# tester.net
KiCad netlist of a schematic drawn in Altium Designer
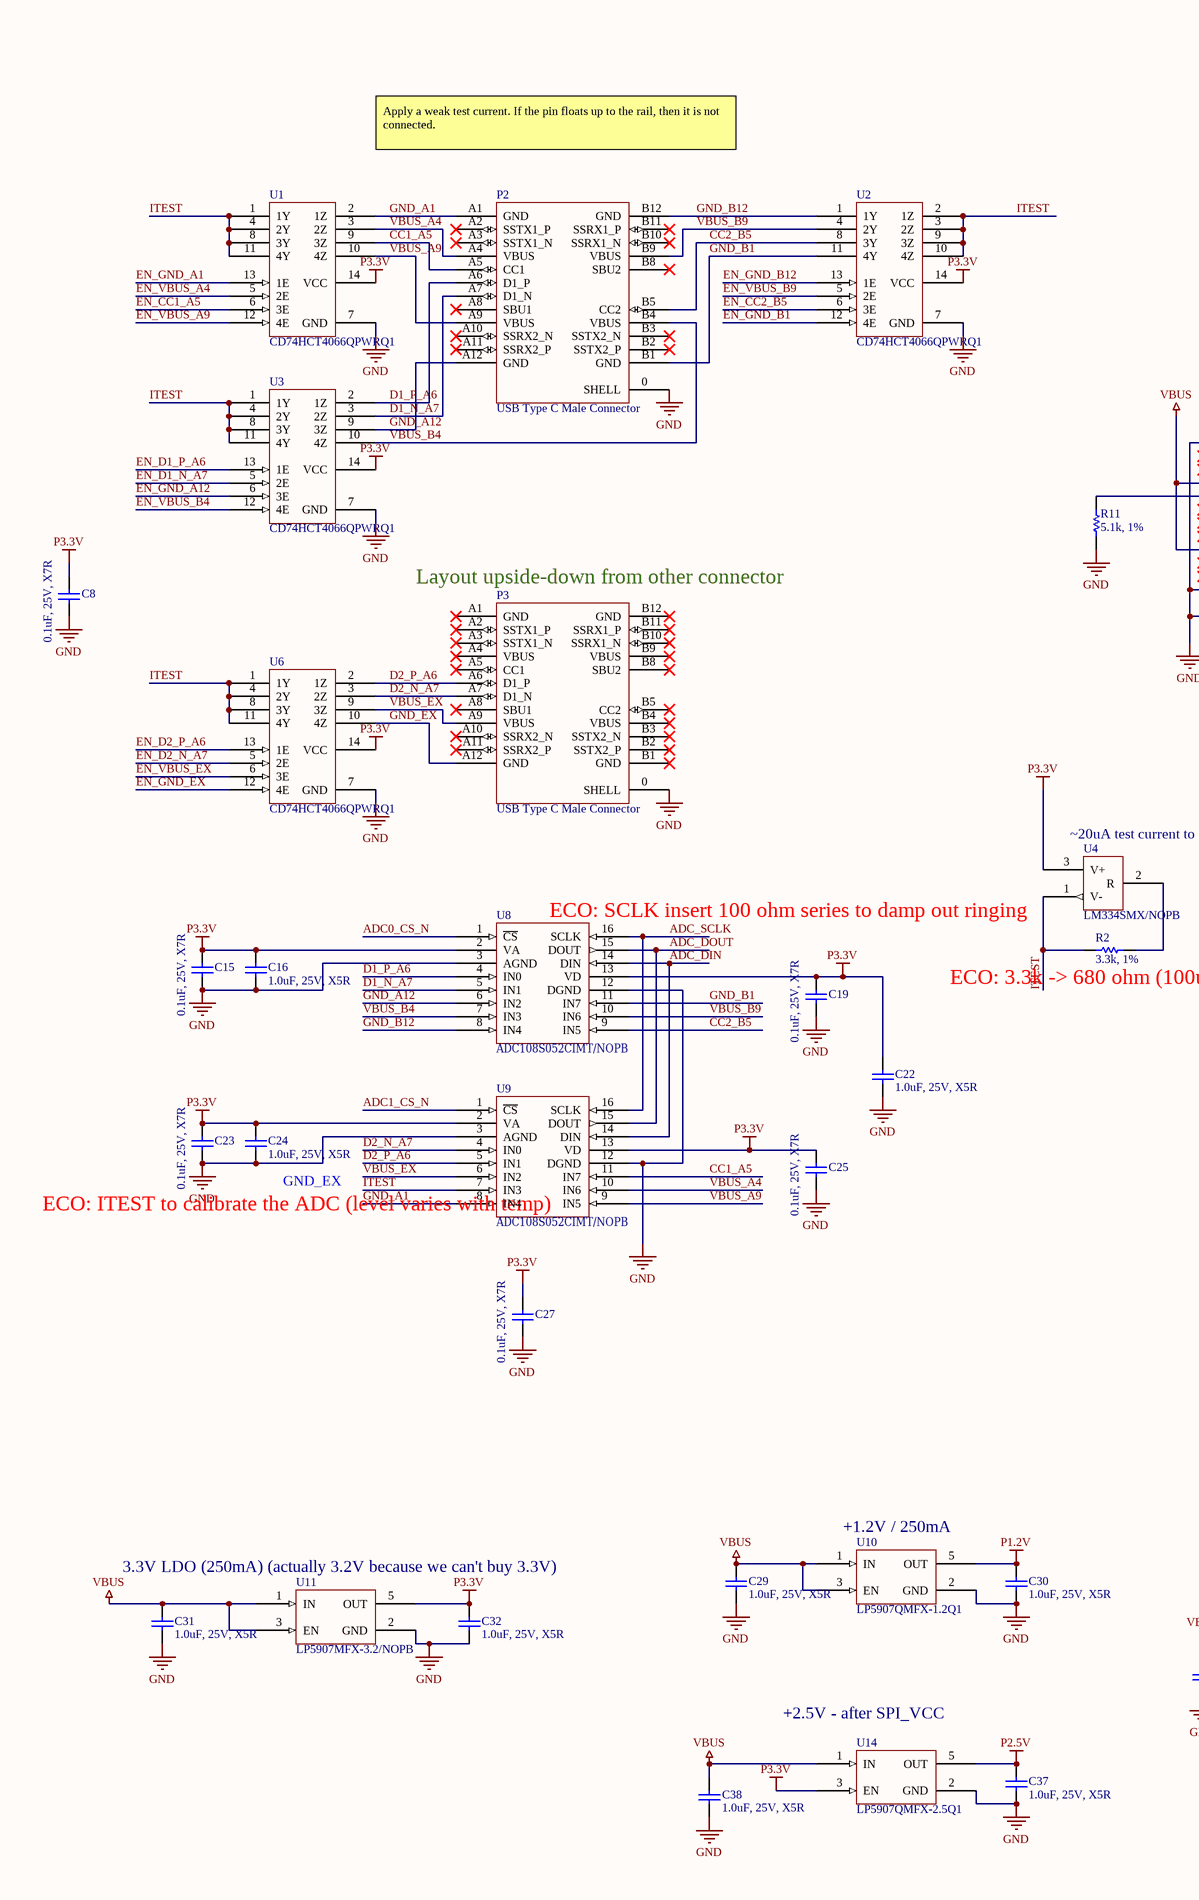
[diagram p0: tester.SchDoc, left]
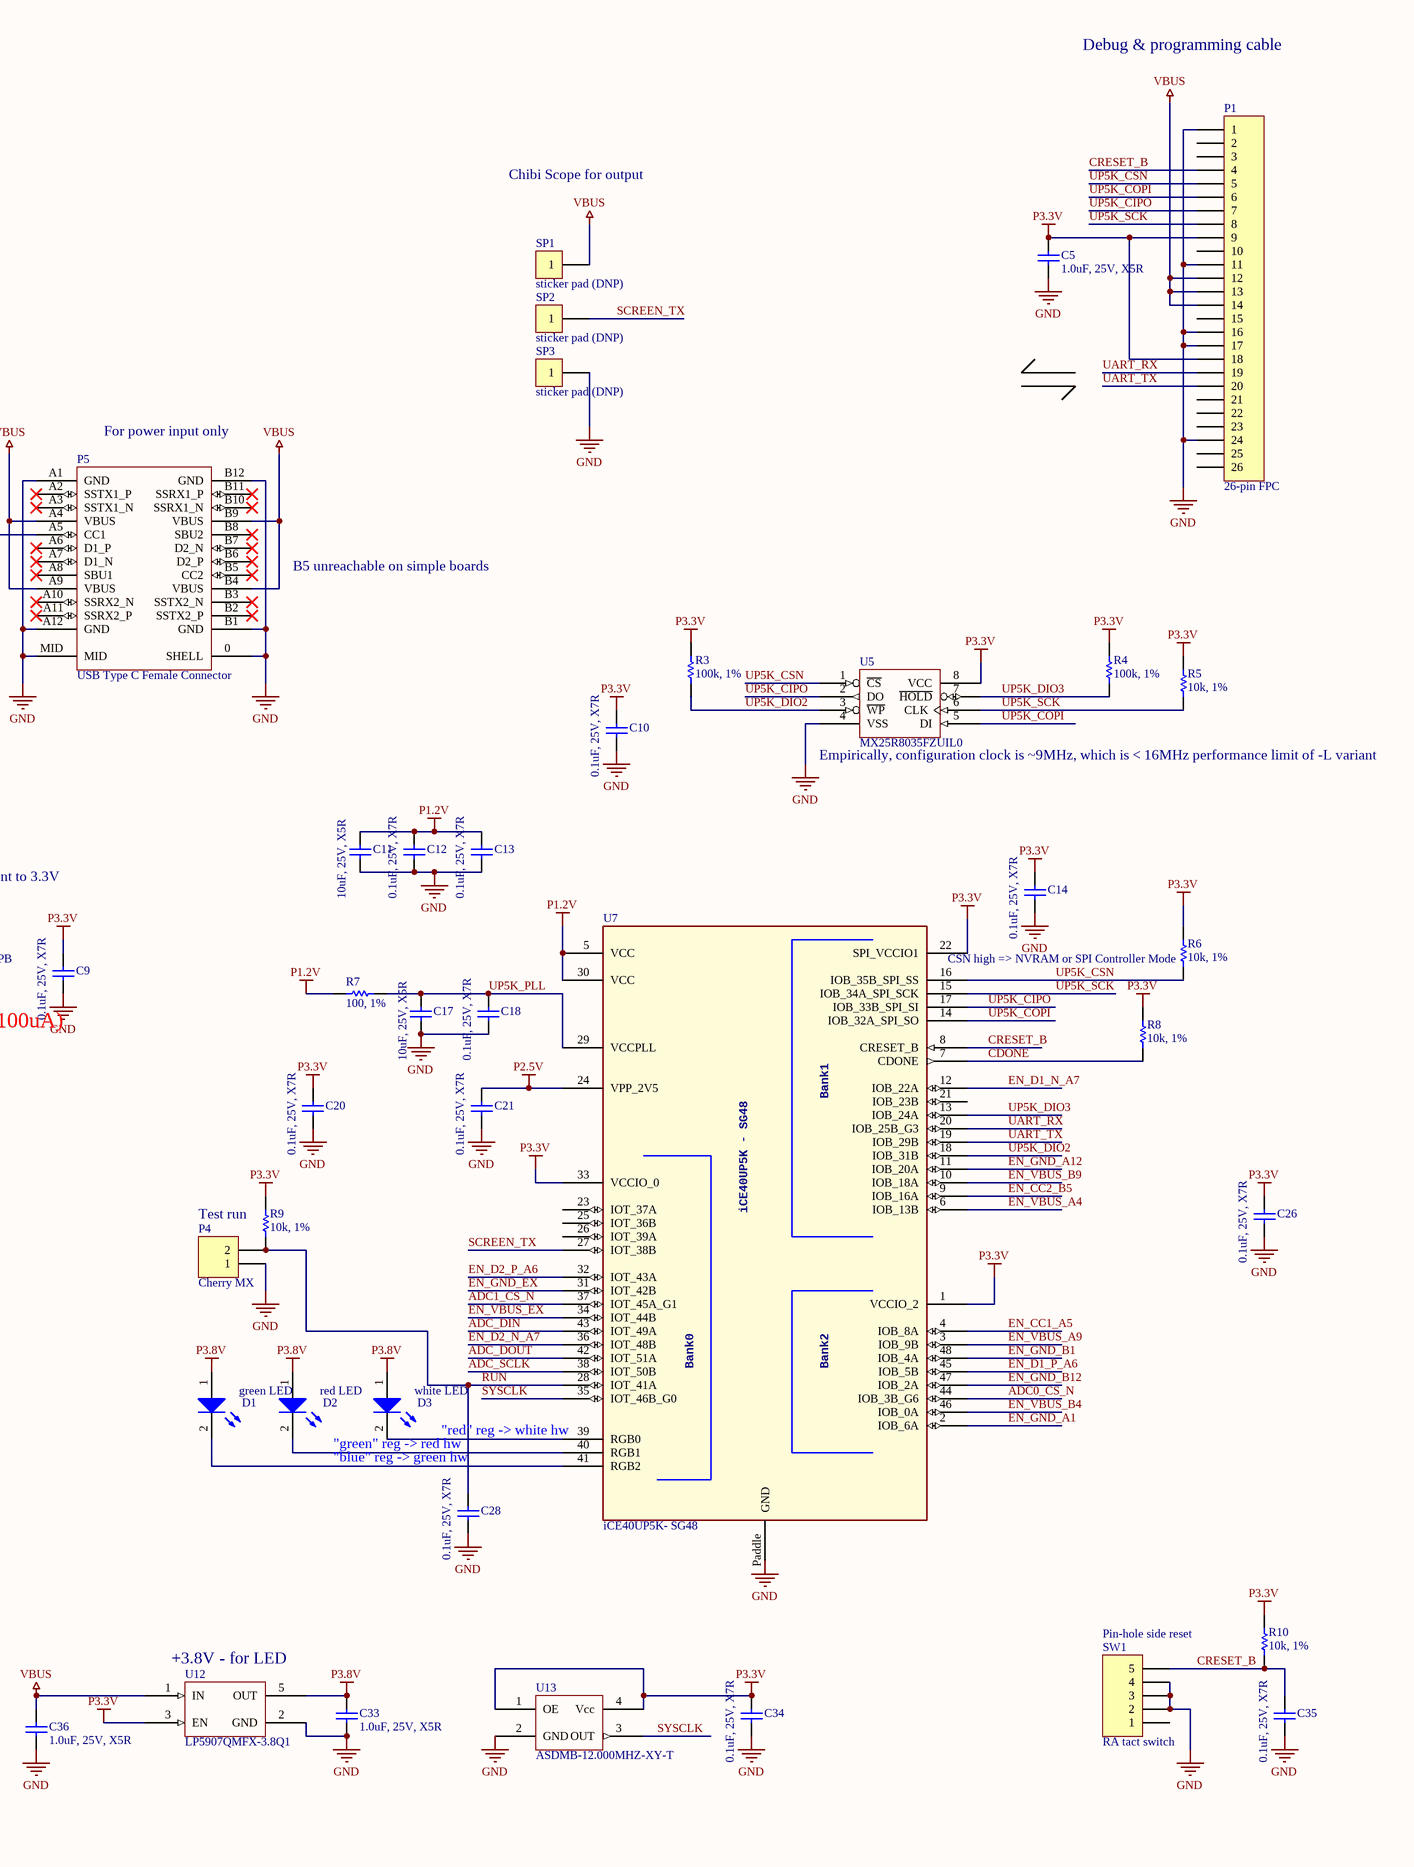
[diagram p1: tester.SchDoc, right]

(export (version "E")
  (design (tool "Eeschema 10.0.6"))
  (components
    (comp (ref "C5")
      (value "1.0uF, 25V, X5R")
      (footprint "B_CAP0603")
      (description "Capacitor (Semiconductor SIM Model)")
      (fields (field (name "MPN") "CL10A105KA8NNNC"))
      (libsource (lib "Miscellaneous Devices") (part "Cap Semi"))
    )
    (comp (ref "C8")
      (value "0.1uF, 25V, X7R")
      (footprint "B_CAP0603")
      (description "Capacitor (Semiconductor SIM Model)")
      (fields (field (name "MPN") "CC0603KRX7R8BB104"))
      (libsource (lib "Miscellaneous Devices") (part "Cap Semi"))
    )
    (comp (ref "C9")
      (value "0.1uF, 25V, X7R")
      (footprint "B_CAP0603")
      (description "Capacitor (Semiconductor SIM Model)")
      (fields (field (name "MPN") "CC0603KRX7R8BB104"))
      (libsource (lib "Miscellaneous Devices") (part "Cap Semi"))
    )
    (comp (ref "C10")
      (value "0.1uF, 25V, X7R")
      (footprint "B_CAP0603")
      (description "Capacitor (Semiconductor SIM Model)")
      (fields (field (name "MPN") "CC0603KRX7R8BB104"))
      (libsource (lib "Miscellaneous Devices") (part "Cap Semi"))
    )
    (comp (ref "C11")
      (value "10uF, 25V, X5R")
      (footprint "B_CAP0805")
      (description "Capacitor (Semiconductor SIM Model)")
      (fields (field (name "MPN") "GRM21BR61E106KA73L"))
      (libsource (lib "Miscellaneous Devices") (part "Cap Semi"))
    )
    (comp (ref "C12")
      (value "0.1uF, 25V, X7R")
      (footprint "B_CAP0603")
      (description "Capacitor (Semiconductor SIM Model)")
      (fields (field (name "MPN") "CC0603KRX7R8BB104"))
      (libsource (lib "Miscellaneous Devices") (part "Cap Semi"))
    )
    (comp (ref "C13")
      (value "0.1uF, 25V, X7R")
      (footprint "B_CAP0603")
      (description "Capacitor (Semiconductor SIM Model)")
      (fields (field (name "MPN") "CC0603KRX7R8BB104"))
      (libsource (lib "Miscellaneous Devices") (part "Cap Semi"))
    )
    (comp (ref "C14")
      (value "0.1uF, 25V, X7R")
      (footprint "B_CAP0603")
      (description "Capacitor (Semiconductor SIM Model)")
      (fields (field (name "MPN") "CC0603KRX7R8BB104"))
      (libsource (lib "Miscellaneous Devices") (part "Cap Semi"))
    )
    (comp (ref "C15")
      (value "0.1uF, 25V, X7R")
      (footprint "B_CAP0603")
      (description "Capacitor (Semiconductor SIM Model)")
      (fields (field (name "MPN") "CC0603KRX7R8BB104"))
      (libsource (lib "Miscellaneous Devices") (part "Cap Semi"))
    )
    (comp (ref "C16")
      (value "1.0uF, 25V, X5R")
      (footprint "B_CAP0603")
      (description "Capacitor (Semiconductor SIM Model)")
      (fields (field (name "MPN") "CL10A105KA8NNNC"))
      (libsource (lib "Miscellaneous Devices") (part "Cap Semi"))
    )
    (comp (ref "C17")
      (value "10uF, 25V, X5R")
      (footprint "B_CAP0805")
      (description "Capacitor (Semiconductor SIM Model)")
      (fields (field (name "MPN") "GRM21BR61E106KA73L"))
      (libsource (lib "Miscellaneous Devices") (part "Cap Semi"))
    )
    (comp (ref "C18")
      (value "0.1uF, 25V, X7R")
      (footprint "B_CAP0603")
      (description "Capacitor (Semiconductor SIM Model)")
      (fields (field (name "MPN") "CC0603KRX7R8BB104"))
      (libsource (lib "Miscellaneous Devices") (part "Cap Semi"))
    )
    (comp (ref "C19")
      (value "0.1uF, 25V, X7R")
      (footprint "B_CAP0603")
      (description "Capacitor (Semiconductor SIM Model)")
      (fields (field (name "MPN") "CC0603KRX7R8BB104"))
      (libsource (lib "Miscellaneous Devices") (part "Cap Semi"))
    )
    (comp (ref "C20")
      (value "0.1uF, 25V, X7R")
      (footprint "B_CAP0603")
      (description "Capacitor (Semiconductor SIM Model)")
      (fields (field (name "MPN") "CC0603KRX7R8BB104"))
      (libsource (lib "Miscellaneous Devices") (part "Cap Semi"))
    )
    (comp (ref "C21")
      (value "0.1uF, 25V, X7R")
      (footprint "B_CAP0603")
      (description "Capacitor (Semiconductor SIM Model)")
      (fields (field (name "MPN") "CC0603KRX7R8BB104"))
      (libsource (lib "Miscellaneous Devices") (part "Cap Semi"))
    )
    (comp (ref "C22")
      (value "1.0uF, 25V, X5R")
      (footprint "B_CAP0603")
      (description "Capacitor (Semiconductor SIM Model)")
      (fields (field (name "MPN") "CL10A105KA8NNNC"))
      (libsource (lib "Miscellaneous Devices") (part "Cap Semi"))
    )
    (comp (ref "C23")
      (value "0.1uF, 25V, X7R")
      (footprint "B_CAP0603")
      (description "Capacitor (Semiconductor SIM Model)")
      (fields (field (name "MPN") "CC0603KRX7R8BB104"))
      (libsource (lib "Miscellaneous Devices") (part "Cap Semi"))
    )
    (comp (ref "C24")
      (value "1.0uF, 25V, X5R")
      (footprint "B_CAP0603")
      (description "Capacitor (Semiconductor SIM Model)")
      (fields (field (name "MPN") "CL10A105KA8NNNC"))
      (libsource (lib "Miscellaneous Devices") (part "Cap Semi"))
    )
    (comp (ref "C25")
      (value "0.1uF, 25V, X7R")
      (footprint "B_CAP0603")
      (description "Capacitor (Semiconductor SIM Model)")
      (fields (field (name "MPN") "CC0603KRX7R8BB104"))
      (libsource (lib "Miscellaneous Devices") (part "Cap Semi"))
    )
    (comp (ref "C26")
      (value "0.1uF, 25V, X7R")
      (footprint "B_CAP0603")
      (description "Capacitor (Semiconductor SIM Model)")
      (fields (field (name "MPN") "CC0603KRX7R8BB104"))
      (libsource (lib "Miscellaneous Devices") (part "Cap Semi"))
    )
    (comp (ref "C27")
      (value "0.1uF, 25V, X7R")
      (footprint "B_CAP0603")
      (description "Capacitor (Semiconductor SIM Model)")
      (fields (field (name "MPN") "CC0603KRX7R8BB104"))
      (libsource (lib "Miscellaneous Devices") (part "Cap Semi"))
    )
    (comp (ref "C28")
      (value "0.1uF, 25V, X7R")
      (footprint "B_CAP0603")
      (description "Capacitor (Semiconductor SIM Model)")
      (fields (field (name "MPN") "CC0603KRX7R8BB104"))
      (libsource (lib "Miscellaneous Devices") (part "Cap Semi"))
    )
    (comp (ref "C29")
      (value "1.0uF, 25V, X5R")
      (footprint "B_CAP0603")
      (description "Capacitor (Semiconductor SIM Model)")
      (fields (field (name "MPN") "CL10A105KA8NNNC"))
      (libsource (lib "Miscellaneous Devices") (part "Cap Semi"))
    )
    (comp (ref "C30")
      (value "1.0uF, 25V, X5R")
      (footprint "B_CAP0603")
      (description "Capacitor (Semiconductor SIM Model)")
      (fields (field (name "MPN") "CL10A105KA8NNNC"))
      (libsource (lib "Miscellaneous Devices") (part "Cap Semi"))
    )
    (comp (ref "C31")
      (value "1.0uF, 25V, X5R")
      (footprint "B_CAP0603")
      (description "Capacitor (Semiconductor SIM Model)")
      (fields (field (name "MPN") "CL10A105KA8NNNC"))
      (libsource (lib "Miscellaneous Devices") (part "Cap Semi"))
    )
    (comp (ref "C32")
      (value "1.0uF, 25V, X5R")
      (footprint "B_CAP0603")
      (description "Capacitor (Semiconductor SIM Model)")
      (fields (field (name "MPN") "CL10A105KA8NNNC"))
      (libsource (lib "Miscellaneous Devices") (part "Cap Semi"))
    )
    (comp (ref "C33")
      (value "1.0uF, 25V, X5R")
      (footprint "B_CAP0603")
      (description "Capacitor (Semiconductor SIM Model)")
      (fields (field (name "MPN") "CL10A105KA8NNNC"))
      (libsource (lib "Miscellaneous Devices") (part "Cap Semi"))
    )
    (comp (ref "C34")
      (value "0.1uF, 25V, X7R")
      (footprint "B_CAP0603")
      (description "Capacitor (Semiconductor SIM Model)")
      (fields (field (name "MPN") "CC0603KRX7R8BB104"))
      (libsource (lib "Miscellaneous Devices") (part "Cap Semi"))
    )
    (comp (ref "C35")
      (value "0.1uF, 25V, X7R")
      (footprint "B_CAP0603")
      (description "Capacitor (Semiconductor SIM Model)")
      (fields (field (name "MPN") "CC0603KRX7R8BB104"))
      (libsource (lib "Miscellaneous Devices") (part "Cap Semi"))
    )
    (comp (ref "C36")
      (value "1.0uF, 25V, X5R")
      (footprint "B_CAP0603")
      (description "Capacitor (Semiconductor SIM Model)")
      (fields (field (name "MPN") "CL10A105KA8NNNC"))
      (libsource (lib "Miscellaneous Devices") (part "Cap Semi"))
    )
    (comp (ref "C37")
      (value "1.0uF, 25V, X5R")
      (footprint "B_CAP0603")
      (description "Capacitor (Semiconductor SIM Model)")
      (fields (field (name "MPN") "CL10A105KA8NNNC"))
      (libsource (lib "Miscellaneous Devices") (part "Cap Semi"))
    )
    (comp (ref "C38")
      (value "1.0uF, 25V, X5R")
      (footprint "B_CAP0603")
      (description "Capacitor (Semiconductor SIM Model)")
      (fields (field (name "MPN") "CL10A105KA8NNNC"))
      (libsource (lib "Miscellaneous Devices") (part "Cap Semi"))
    )
    (comp (ref "D1")
      (value "green LED")
      (footprint "B_LED0805")
      (description "Typical RED, GREEN, YELLOW, AMBER GaAs LED")
      (fields (field (name "MPN") "IN-S85ATG"))
      (libsource (lib "Miscellaneous Devices") (part "LED2"))
    )
    (comp (ref "D2")
      (value "red LED")
      (footprint "B_LED0805")
      (description "Typical RED, GREEN, YELLOW, AMBER GaAs LED")
      (fields (field (name "MPN") "IN-S85ATR"))
      (libsource (lib "Miscellaneous Devices") (part "LED2"))
    )
    (comp (ref "D3")
      (value "white LED")
      (footprint "B_LED0805")
      (description "Typical RED, GREEN, YELLOW, AMBER GaAs LED")
      (fields (field (name "MPN") "IN-S85AT5UW"))
      (libsource (lib "Miscellaneous Devices") (part "LED2"))
    )
    (comp (ref "P1")
      (value "26-pin FPC")
      (footprint "HRS_FH34SRJ-26S-0.5SH(50)")
      (description "26 Pin FPC header")
      (fields (field (name "MPN") "FH34SRJ-26S-0.5SH(99)"))
      (libsource (lib "commonsch-new") (part "FPC-26"))
    )
    (comp (ref "P2")
      (value "USB Type C Male Connector")
      (footprint "MOLEX_1054440001")
      (description "USB Type C Connector")
      (fields (field (name "MPN") "1054440011"))
      (libsource (lib "") (part "USB_TYPE_C_1"))
    )
    (comp (ref "P3")
      (value "USB Type C Male Connector")
      (footprint "MOLEX_1054440001")
      (description "USB Type C Connector")
      (fields (field (name "MPN") "1054440011"))
      (libsource (lib "") (part "USB_TYPE_C_1"))
    )
    (comp (ref "P4")
      (value "Cherry MX")
      (footprint "CHERRY_MX_BASIC")
      (description "Header, 2-Pin")
      (fields (field (name "MPN") "MX1A-E1NN") (field (name "PUBLISHER") "Altium Limited"))
      (libsource (lib "Miscellaneous Connectors") (part "Header 2"))
    )
    (comp (ref "P5")
      (value "USB Type C Female Connector")
      (footprint "TE_1-2295018-2")
      (description "USB Type C Connector")
      (fields (field (name "MPN") "1-2295018-2"))
      (libsource (lib "commonsch-new") (part "USB_TYPE_C"))
    )
    (comp (ref "R2")
      (value "3.3k, 1%")
      (footprint "B_RES0402")
      (description "Resistor")
      (fields (field (name "MPN") "TBD"))
      (libsource (lib "Miscellaneous Devices") (part "Res1"))
    )
    (comp (ref "R3")
      (value "100k, 1%")
      (footprint "B_RES0603")
      (description "Resistor")
      (fields (field (name "MPN") "TBD"))
      (libsource (lib "Miscellaneous Devices") (part "Res1"))
    )
    (comp (ref "R4")
      (value "100k, 1%")
      (footprint "B_RES0603")
      (description "Resistor")
      (fields (field (name "MPN") "TBD"))
      (libsource (lib "Miscellaneous Devices") (part "Res1"))
    )
    (comp (ref "R5")
      (value "10k, 1%")
      (footprint "B_RES0603")
      (description "Resistor")
      (fields (field (name "MPN") "RC0603FR-0710KL"))
      (libsource (lib "Miscellaneous Devices") (part "Res1"))
    )
    (comp (ref "R6")
      (value "10k, 1%")
      (footprint "B_RES0603")
      (description "Resistor")
      (fields (field (name "MPN") "RC0603FR-0710KL"))
      (libsource (lib "Miscellaneous Devices") (part "Res1"))
    )
    (comp (ref "R7")
      (value "100, 1%")
      (footprint "B_RES0603")
      (description "Resistor")
      (fields (field (name "MPN") "TBD"))
      (libsource (lib "Miscellaneous Devices") (part "Res1"))
    )
    (comp (ref "R8")
      (value "10k, 1%")
      (footprint "B_RES0603")
      (description "Resistor")
      (fields (field (name "MPN") "RC0603FR-0710KL"))
      (libsource (lib "Miscellaneous Devices") (part "Res1"))
    )
    (comp (ref "R9")
      (value "10k, 1%")
      (footprint "B_RES0603")
      (description "Resistor")
      (fields (field (name "MPN") "RC0603FR-0710KL"))
      (libsource (lib "Miscellaneous Devices") (part "Res1"))
    )
    (comp (ref "R10")
      (value "10k, 1%")
      (footprint "B_RES0603")
      (description "Resistor")
      (fields (field (name "MPN") "RC0603FR-0710KL"))
      (libsource (lib "Miscellaneous Devices") (part "Res1"))
    )
    (comp (ref "R11")
      (value "5.1k, 1%")
      (footprint "B_RES0603")
      (description "Resistor")
      (fields (field (name "MPN") "RC0603FR-075K1L"))
      (libsource (lib "Miscellaneous Devices") (part "Res1"))
    )
    (comp (ref "SP1")
      (value "sticker pad (DNP)")
      (footprint "TP_SMT_38mil")
      (description "Connector")
      (libsource (lib "*") (part "CON1"))
    )
    (comp (ref "SP2")
      (value "sticker pad (DNP)")
      (footprint "TP_SMT_38mil")
      (description "Connector")
      (libsource (lib "*") (part "CON1"))
    )
    (comp (ref "SP3")
      (value "sticker pad (DNP)")
      (footprint "TP_SMT_38mil")
      (description "Connector")
      (libsource (lib "*") (part "CON1"))
    )
    (comp (ref "SW1")
      (value "RA tact switch")
      (footprint "CK_KMS221GPLFS")
      (fields (field (name "MPN") "KMS221GPLFS") (field (name "PUBLISHER") "Altium Limited"))
      (libsource (lib "Miscellaneous Connectors") (part "Header 5"))
    )
    (comp (ref "U1")
      (value "CD74HCT4066QPWRQ1")
      (footprint "TSOP65P640-14AN")
      (description "4-channel analog mux")
      (libsource (lib "commonsch") (part "74HC4066"))
    )
    (comp (ref "U2")
      (value "CD74HCT4066QPWRQ1")
      (footprint "TSOP65P640-14AN")
      (description "4-channel analog mux")
      (libsource (lib "commonsch") (part "74HC4066"))
    )
    (comp (ref "U3")
      (value "CD74HCT4066QPWRQ1")
      (footprint "TSOP65P640-14AN")
      (description "4-channel analog mux")
      (libsource (lib "commonsch") (part "74HC4066"))
    )
    (comp (ref "U4")
      (value "LM334SMX/NOPB")
      (footprint "SOIC127P600-8AN")
      (description "LM134/234/334 3-terminal adjustable current sources")
      (libsource (lib "commonsch-new") (part "LMx34"))
    )
    (comp (ref "U5")
      (value "MX25R8035FZUIL0")
      (footprint "USON-8")
      (description "64Mbit SPI NOR FLASH")
      (libsource (lib "commonsch") (part "EN25P05-50GCP"))
    )
    (comp (ref "U6")
      (value "CD74HCT4066QPWRQ1")
      (footprint "TSOP65P640-14AN")
      (description "4-channel analog mux")
      (libsource (lib "commonsch") (part "74HC4066"))
    )
    (comp (ref "U7")
      (value "iCE40UP5K- SG48")
      (footprint "UP5K_QFN127P600-8N")
      (fields (field (name "MPN") "ICE40UP5K-SG48I"))
      (libsource (lib "LATTICEPLDS_Library") (part "iCE40UP5K- SG48"))
    )
    (comp (ref "U8")
      (value "ADC108S052CIMT/NOPB‎")
      (footprint "SOP65P640-16N")
      (description "12-input SPI ADC, bits & sample rate pin compatible across family")
      (fields (field (name "MPN") "ADC088S022CIMT/NOPB-ND"))
      (libsource (lib "commonsch") (part "ADCxx8Sxx2"))
    )
    (comp (ref "U9")
      (value "ADC108S052CIMT/NOPB‎")
      (footprint "SOP65P640-16N")
      (description "12-input SPI ADC, bits & sample rate pin compatible across family")
      (fields (field (name "MPN") "ADC088S022CIMT/NOPB-ND"))
      (libsource (lib "commonsch") (part "ADCxx8Sxx2"))
    )
    (comp (ref "U10")
      (value "LP5907QMFX-1.2Q1")
      (footprint "SOT23-5AN")
      (description "Ultra low-noise 250mA LDO for RF and analog in SOT23-5")
      (fields (field (name "MPN") "LP5907UVX-#.#/NOPB"))
      (libsource (lib "commonsch-new") (part "LP5907QMFX-XX"))
    )
    (comp (ref "U11")
      (value "LP5907MFX-3.2/NOPB")
      (footprint "SOT23-5AN")
      (description "Ultra low-noise 250mA LDO for RF and analog in SOT23-5")
      (fields (field (name "MPN") "LP5907UVX-#.#/NOPB"))
      (libsource (lib "commonsch-new") (part "LP5907QMFX-XX"))
    )
    (comp (ref "U12")
      (value "LP5907QMFX-3.8Q1")
      (footprint "SOT23-5AN")
      (description "Ultra low-noise 250mA LDO for RF and analog in SOT23-5")
      (fields (field (name "MPN") "LP5907UVX-#.#/NOPB"))
      (libsource (lib "commonsch-new") (part "LP5907QMFX-XX"))
    )
    (comp (ref "U13")
      (value "ASDMB-12.000MHZ-XY-T")
      (footprint "ABRACON_ASDMB")
      (description "Abracon ASDMB Miniature Oscillator")
      (libsource (lib "commonsch") (part "OSCILLATOR"))
    )
    (comp (ref "U14")
      (value "LP5907QMFX-2.5Q1")
      (footprint "SOT23-5AN")
      (description "Ultra low-noise 250mA LDO for RF and analog in SOT23-5")
      (fields (field (name "MPN") "LP5907UVX-#.#/NOPB"))
      (libsource (lib "commonsch-new") (part "LP5907QMFX-XX"))
    )
  )
  (nets
    (net (code "1") (name "/ADC0_CS_N") (class "Default")
      (node (ref "U7") (pin "44") (pinfunction "IOB_3B_G6_44") (pintype "bidirectional"))
      (node (ref "U8") (pin "1") (pinfunction "~{CS}_1") (pintype "input"))
    )
    (net (code "2") (name "/ADC1_CS_N") (class "Default")
      (node (ref "U7") (pin "37") (pinfunction "IOT_45A_G1_37") (pintype "bidirectional"))
      (node (ref "U9") (pin "1") (pinfunction "~{CS}_1") (pintype "input"))
    )
    (net (code "3") (name "/ADC_DIN") (class "Default")
      (node (ref "U7") (pin "43") (pinfunction "IOT_49A_43") (pintype "bidirectional"))
      (node (ref "U8") (pin "14") (pinfunction "DIN_14") (pintype "input"))
      (node (ref "U9") (pin "14") (pinfunction "DIN_14") (pintype "input"))
    )
    (net (code "4") (name "/ADC_DOUT") (class "Default")
      (node (ref "U7") (pin "42") (pinfunction "IOT_51A_42") (pintype "bidirectional"))
      (node (ref "U8") (pin "15") (pinfunction "DOUT_15") (pintype "output"))
      (node (ref "U9") (pin "15") (pinfunction "DOUT_15") (pintype "output"))
    )
    (net (code "5") (name "/ADC_SCLK") (class "Default")
      (node (ref "U7") (pin "38") (pinfunction "IOT_50B_38") (pintype "bidirectional"))
      (node (ref "U8") (pin "16") (pinfunction "SCLK_16") (pintype "input"))
      (node (ref "U9") (pin "16") (pinfunction "SCLK_16") (pintype "input"))
    )
    (net (code "6") (name "/CC1_A5") (class "Default")
      (node (ref "P2") (pin "A5") (pinfunction "CC1_A5") (pintype "bidirectional"))
      (node (ref "U1") (pin "9") (pinfunction "3Z_9") (pintype "passive"))
      (node (ref "U9") (pin "11") (pinfunction "IN7_11") (pintype "input"))
    )
    (net (code "7") (name "/CC2_B5") (class "Default")
      (node (ref "P2") (pin "B5") (pinfunction "CC2_B5") (pintype "bidirectional"))
      (node (ref "U2") (pin "8") (pinfunction "3Y_8") (pintype "passive"))
      (node (ref "U8") (pin "9") (pinfunction "IN5_9") (pintype "input"))
    )
    (net (code "8") (name "/CDONE") (class "Default")
      (node (ref "R8") (pin "2") (pinfunction "2_2") (pintype "passive"))
      (node (ref "U7") (pin "7") (pinfunction "CDONE_7") (pintype "output"))
    )
    (net (code "9") (name "/CRESET_B") (class "Default")
      (node (ref "C35") (pin "1") (pinfunction "1_1") (pintype "passive"))
      (node (ref "P1") (pin "4") (pinfunction "4_4") (pintype "passive"))
      (node (ref "R10") (pin "2") (pinfunction "2_2") (pintype "passive"))
      (node (ref "SW1") (pin "5") (pinfunction "5_5") (pintype "passive"))
      (node (ref "U7") (pin "8") (pinfunction "CRESET_B_8") (pintype "input"))
    )
    (net (code "10") (name "/D1_N_A7") (class "Default")
      (node (ref "P2") (pin "A7") (pinfunction "D1_N_A7") (pintype "bidirectional"))
      (node (ref "U3") (pin "3") (pinfunction "2Z_3") (pintype "passive"))
      (node (ref "U8") (pin "5") (pinfunction "IN1_5") (pintype "input"))
    )
    (net (code "11") (name "/D1_P_A6") (class "Default")
      (node (ref "P2") (pin "A6") (pinfunction "D1_P_A6") (pintype "bidirectional"))
      (node (ref "U3") (pin "2") (pinfunction "1Z_2") (pintype "passive"))
      (node (ref "U8") (pin "4") (pinfunction "IN0_4") (pintype "input"))
    )
    (net (code "12") (name "/D2_N_A7") (class "Default")
      (node (ref "P3") (pin "A7") (pinfunction "D1_N_A7") (pintype "bidirectional"))
      (node (ref "U6") (pin "3") (pinfunction "2Z_3") (pintype "passive"))
      (node (ref "U9") (pin "4") (pinfunction "IN0_4") (pintype "input"))
    )
    (net (code "13") (name "/D2_P_A6") (class "Default")
      (node (ref "P3") (pin "A6") (pinfunction "D1_P_A6") (pintype "bidirectional"))
      (node (ref "U6") (pin "2") (pinfunction "1Z_2") (pintype "passive"))
      (node (ref "U9") (pin "5") (pinfunction "IN1_5") (pintype "input"))
    )
    (net (code "14") (name "/EN_CC1_A5") (class "Default")
      (node (ref "U1") (pin "6") (pinfunction "3E_6") (pintype "input"))
      (node (ref "U7") (pin "4") (pinfunction "IOB_8A_4") (pintype "bidirectional"))
    )
    (net (code "15") (name "/EN_CC2_B5") (class "Default")
      (node (ref "U2") (pin "6") (pinfunction "3E_6") (pintype "input"))
      (node (ref "U7") (pin "9") (pinfunction "IOB_16A_9") (pintype "bidirectional"))
    )
    (net (code "16") (name "/EN_D1_N_A7") (class "Default")
      (node (ref "U3") (pin "5") (pinfunction "2E_5") (pintype "input"))
      (node (ref "U7") (pin "12") (pinfunction "IOB_22A_12") (pintype "bidirectional"))
    )
    (net (code "17") (name "/EN_D1_P_A6") (class "Default")
      (node (ref "U3") (pin "13") (pinfunction "1E_13") (pintype "input"))
      (node (ref "U7") (pin "45") (pinfunction "IOB_5B_45") (pintype "bidirectional"))
    )
    (net (code "18") (name "/EN_D2_N_A7") (class "Default")
      (node (ref "U6") (pin "5") (pinfunction "2E_5") (pintype "input"))
      (node (ref "U7") (pin "36") (pinfunction "IOT_48B_36") (pintype "bidirectional"))
    )
    (net (code "19") (name "/EN_D2_P_A6") (class "Default")
      (node (ref "U6") (pin "13") (pinfunction "1E_13") (pintype "input"))
      (node (ref "U7") (pin "32") (pinfunction "IOT_43A_32") (pintype "bidirectional"))
    )
    (net (code "20") (name "/EN_GND_A1") (class "Default")
      (node (ref "U1") (pin "13") (pinfunction "1E_13") (pintype "input"))
      (node (ref "U7") (pin "2") (pinfunction "IOB_6A_2") (pintype "bidirectional"))
    )
    (net (code "21") (name "/EN_GND_A12") (class "Default")
      (node (ref "U3") (pin "6") (pinfunction "3E_6") (pintype "input"))
      (node (ref "U7") (pin "11") (pinfunction "IOB_20A_11") (pintype "bidirectional"))
    )
    (net (code "22") (name "/EN_GND_B1") (class "Default")
      (node (ref "U2") (pin "12") (pinfunction "4E_12") (pintype "input"))
      (node (ref "U7") (pin "48") (pinfunction "IOB_4A_48") (pintype "bidirectional"))
    )
    (net (code "23") (name "/EN_GND_B12") (class "Default")
      (node (ref "U2") (pin "13") (pinfunction "1E_13") (pintype "input"))
      (node (ref "U7") (pin "47") (pinfunction "IOB_2A_47") (pintype "bidirectional"))
    )
    (net (code "24") (name "/EN_GND_EX") (class "Default")
      (node (ref "U6") (pin "12") (pinfunction "4E_12") (pintype "input"))
      (node (ref "U7") (pin "31") (pinfunction "IOT_42B_31") (pintype "bidirectional"))
    )
    (net (code "25") (name "/EN_VBUS_A4") (class "Default")
      (node (ref "U1") (pin "5") (pinfunction "2E_5") (pintype "input"))
      (node (ref "U7") (pin "6") (pinfunction "IOB_13B_6") (pintype "bidirectional"))
    )
    (net (code "26") (name "/EN_VBUS_A9") (class "Default")
      (node (ref "U1") (pin "12") (pinfunction "4E_12") (pintype "input"))
      (node (ref "U7") (pin "3") (pinfunction "IOB_9B_3") (pintype "bidirectional"))
    )
    (net (code "27") (name "/EN_VBUS_B4") (class "Default")
      (node (ref "U3") (pin "12") (pinfunction "4E_12") (pintype "input"))
      (node (ref "U7") (pin "46") (pinfunction "IOB_0A_46") (pintype "bidirectional"))
    )
    (net (code "28") (name "/EN_VBUS_B9") (class "Default")
      (node (ref "U2") (pin "5") (pinfunction "2E_5") (pintype "input"))
      (node (ref "U7") (pin "10") (pinfunction "IOB_18A_10") (pintype "bidirectional"))
    )
    (net (code "29") (name "/EN_VBUS_EX") (class "Default")
      (node (ref "U6") (pin "6") (pinfunction "3E_6") (pintype "input"))
      (node (ref "U7") (pin "34") (pinfunction "IOT_44B_34") (pintype "bidirectional"))
    )
    (net (code "30") (name "/GND_A1") (class "Default")
      (node (ref "P2") (pin "A1") (pinfunction "GND_A1") (pintype "power_in"))
      (node (ref "U1") (pin "2") (pinfunction "1Z_2") (pintype "passive"))
      (node (ref "U9") (pin "8") (pinfunction "IN4_8") (pintype "input"))
    )
    (net (code "31") (name "/GND_A12") (class "Default")
      (node (ref "P2") (pin "A12") (pinfunction "GND_A12") (pintype "power_in"))
      (node (ref "U3") (pin "9") (pinfunction "3Z_9") (pintype "passive"))
      (node (ref "U8") (pin "6") (pinfunction "IN2_6") (pintype "input"))
    )
    (net (code "32") (name "/GND_B1") (class "Default")
      (node (ref "P2") (pin "B1") (pinfunction "GND_B1") (pintype "power_in"))
      (node (ref "U2") (pin "11") (pinfunction "4Y_11") (pintype "passive"))
      (node (ref "U8") (pin "11") (pinfunction "IN7_11") (pintype "input"))
    )
    (net (code "33") (name "/GND_B12") (class "Default")
      (node (ref "P2") (pin "B12") (pinfunction "GND_B12") (pintype "power_in"))
      (node (ref "U2") (pin "1") (pinfunction "1Y_1") (pintype "passive"))
      (node (ref "U8") (pin "8") (pinfunction "IN4_8") (pintype "input"))
    )
    (net (code "34") (name "/GND_EX") (class "Default")
      (node (ref "P3") (pin "A12") (pinfunction "GND_A12") (pintype "power_in"))
      (node (ref "U6") (pin "10") (pinfunction "4Z_10") (pintype "passive"))
    )
    (net (code "35") (name "/ITEST") (class "Default")
      (node (ref "R2") (pin "1") (pinfunction "1_1") (pintype "passive"))
      (node (ref "U1") (pin "1") (pinfunction "1Y_1") (pintype "passive"))
      (node (ref "U1") (pin "11") (pinfunction "4Y_11") (pintype "passive"))
      (node (ref "U1") (pin "4") (pinfunction "2Y_4") (pintype "passive"))
      (node (ref "U1") (pin "8") (pinfunction "3Y_8") (pintype "passive"))
      (node (ref "U2") (pin "10") (pinfunction "4Z_10") (pintype "passive"))
      (node (ref "U2") (pin "2") (pinfunction "1Z_2") (pintype "passive"))
      (node (ref "U2") (pin "3") (pinfunction "2Z_3") (pintype "passive"))
      (node (ref "U2") (pin "9") (pinfunction "3Z_9") (pintype "passive"))
      (node (ref "U3") (pin "1") (pinfunction "1Y_1") (pintype "passive"))
      (node (ref "U3") (pin "11") (pinfunction "4Y_11") (pintype "passive"))
      (node (ref "U3") (pin "4") (pinfunction "2Y_4") (pintype "passive"))
      (node (ref "U3") (pin "8") (pinfunction "3Y_8") (pintype "passive"))
      (node (ref "U4") (pin "1") (pinfunction "V-_1") (pintype "output"))
      (node (ref "U6") (pin "1") (pinfunction "1Y_1") (pintype "passive"))
      (node (ref "U6") (pin "11") (pinfunction "4Y_11") (pintype "passive"))
      (node (ref "U6") (pin "4") (pinfunction "2Y_4") (pintype "passive"))
      (node (ref "U6") (pin "8") (pinfunction "3Y_8") (pintype "passive"))
      (node (ref "U9") (pin "7") (pinfunction "IN3_7") (pintype "input"))
    )
    (net (code "36") (name "/RUN") (class "Default")
      (node (ref "C28") (pin "1") (pinfunction "1_1") (pintype "passive"))
      (node (ref "P4") (pin "2") (pinfunction "2_2") (pintype "passive"))
      (node (ref "R9") (pin "2") (pinfunction "2_2") (pintype "passive"))
      (node (ref "U7") (pin "28") (pinfunction "IOT_41A_28") (pintype "bidirectional"))
    )
    (net (code "37") (name "/SCREEN_TX") (class "Default")
      (node (ref "SP2") (pin "1") (pinfunction "1_1") (pintype "passive"))
      (node (ref "U7") (pin "27") (pinfunction "IOT_38B_27") (pintype "bidirectional"))
    )
    (net (code "38") (name "/SYSCLK") (class "Default")
      (node (ref "U13") (pin "3") (pinfunction "OUT_3") (pintype "output"))
      (node (ref "U7") (pin "35") (pinfunction "IOT_46B_G0_35") (pintype "bidirectional"))
    )
    (net (code "39") (name "/UART_RX") (class "Default")
      (node (ref "P1") (pin "19") (pinfunction "19_19") (pintype "passive"))
      (node (ref "U7") (pin "20") (pinfunction "IOB_25B_G3_20") (pintype "bidirectional"))
    )
    (net (code "40") (name "/UART_TX") (class "Default")
      (node (ref "P1") (pin "20") (pinfunction "20_20") (pintype "passive"))
      (node (ref "U7") (pin "19") (pinfunction "IOB_29B_19") (pintype "bidirectional"))
    )
    (net (code "41") (name "/UP5K_CIPO") (class "Default")
      (node (ref "P1") (pin "7") (pinfunction "7_7") (pintype "passive"))
      (node (ref "U5") (pin "2") (pinfunction "DO_2") (pintype "output"))
      (node (ref "U7") (pin "17") (pinfunction "IOB_33B_SPI_SI_17") (pintype "passive"))
    )
    (net (code "42") (name "/UP5K_COPI") (class "Default")
      (node (ref "P1") (pin "6") (pinfunction "6_6") (pintype "passive"))
      (node (ref "U5") (pin "5") (pinfunction "DI_5") (pintype "input"))
      (node (ref "U7") (pin "14") (pinfunction "IOB_32A_SPI_SO_14") (pintype "passive"))
    )
    (net (code "43") (name "/UP5K_CSN") (class "Default")
      (node (ref "P1") (pin "5") (pinfunction "5_5") (pintype "passive"))
      (node (ref "R6") (pin "2") (pinfunction "2_2") (pintype "passive"))
      (node (ref "U5") (pin "1") (pinfunction "~{CS}_1") (pintype "input"))
      (node (ref "U7") (pin "16") (pinfunction "IOB_35B_SPI_SS_16") (pintype "passive"))
    )
    (net (code "44") (name "/UP5K_DIO2") (class "Default")
      (node (ref "R3") (pin "2") (pinfunction "2_2") (pintype "passive"))
      (node (ref "U5") (pin "3") (pinfunction "~{WP}_3") (pintype "input"))
      (node (ref "U7") (pin "18") (pinfunction "IOB_31B_18") (pintype "bidirectional"))
    )
    (net (code "45") (name "/UP5K_DIO3") (class "Default")
      (node (ref "R4") (pin "2") (pinfunction "2_2") (pintype "passive"))
      (node (ref "U5") (pin "7") (pinfunction "~{HOLD}_7") (pintype "bidirectional"))
      (node (ref "U7") (pin "13") (pinfunction "IOB_24A_13") (pintype "bidirectional"))
    )
    (net (code "46") (name "/UP5K_PLL") (class "Default")
      (node (ref "C17") (pin "1") (pinfunction "1_1") (pintype "passive"))
      (node (ref "C18") (pin "1") (pinfunction "1_1") (pintype "passive"))
      (node (ref "R7") (pin "2") (pinfunction "2_2") (pintype "passive"))
      (node (ref "U7") (pin "29") (pinfunction "VCCPLL_29") (pintype "power_in"))
    )
    (net (code "47") (name "/UP5K_SCK") (class "Default")
      (node (ref "P1") (pin "8") (pinfunction "8_8") (pintype "passive"))
      (node (ref "R5") (pin "2") (pinfunction "2_2") (pintype "passive"))
      (node (ref "U5") (pin "6") (pinfunction "CLK_6") (pintype "input"))
      (node (ref "U7") (pin "15") (pinfunction "IOB_34A_SPI_SCK_15") (pintype "passive"))
    )
    (net (code "48") (name "/VBUS_A4") (class "Default")
      (node (ref "P2") (pin "A4") (pinfunction "VBUS_A4") (pintype "power_in"))
      (node (ref "U1") (pin "3") (pinfunction "2Z_3") (pintype "passive"))
      (node (ref "U9") (pin "10") (pinfunction "IN6_10") (pintype "input"))
    )
    (net (code "49") (name "/VBUS_A9") (class "Default")
      (node (ref "P2") (pin "A9") (pinfunction "VBUS_A9") (pintype "power_in"))
      (node (ref "U1") (pin "10") (pinfunction "4Z_10") (pintype "passive"))
      (node (ref "U9") (pin "9") (pinfunction "IN5_9") (pintype "input"))
    )
    (net (code "50") (name "/VBUS_B4") (class "Default")
      (node (ref "P2") (pin "B4") (pinfunction "VBUS_B4") (pintype "power_in"))
      (node (ref "U3") (pin "10") (pinfunction "4Z_10") (pintype "passive"))
      (node (ref "U8") (pin "7") (pinfunction "IN3_7") (pintype "input"))
    )
    (net (code "51") (name "/VBUS_B9") (class "Default")
      (node (ref "P2") (pin "B9") (pinfunction "VBUS_B9") (pintype "power_in"))
      (node (ref "U2") (pin "4") (pinfunction "2Y_4") (pintype "passive"))
      (node (ref "U8") (pin "10") (pinfunction "IN6_10") (pintype "input"))
    )
    (net (code "52") (name "/VBUS_EX") (class "Default")
      (node (ref "P3") (pin "A9") (pinfunction "VBUS_A9") (pintype "power_in"))
      (node (ref "U6") (pin "9") (pinfunction "3Z_9") (pintype "passive"))
      (node (ref "U9") (pin "6") (pinfunction "IN2_6") (pintype "input"))
    )
    (net (code "53") (name "GND") (class "Default")
      (node (ref "C10") (pin "2") (pinfunction "2_2") (pintype "passive"))
      (node (ref "C11") (pin "2") (pinfunction "2_2") (pintype "passive"))
      (node (ref "C12") (pin "2") (pinfunction "2_2") (pintype "passive"))
      (node (ref "C13") (pin "2") (pinfunction "2_2") (pintype "passive"))
      (node (ref "C14") (pin "2") (pinfunction "2_2") (pintype "passive"))
      (node (ref "C15") (pin "2") (pinfunction "2_2") (pintype "passive"))
      (node (ref "C16") (pin "1") (pinfunction "1_1") (pintype "passive"))
      (node (ref "C17") (pin "2") (pinfunction "2_2") (pintype "passive"))
      (node (ref "C18") (pin "2") (pinfunction "2_2") (pintype "passive"))
      (node (ref "C19") (pin "2") (pinfunction "2_2") (pintype "passive"))
      (node (ref "C20") (pin "2") (pinfunction "2_2") (pintype "passive"))
      (node (ref "C21") (pin "2") (pinfunction "2_2") (pintype "passive"))
      (node (ref "C22") (pin "1") (pinfunction "1_1") (pintype "passive"))
      (node (ref "C23") (pin "2") (pinfunction "2_2") (pintype "passive"))
      (node (ref "C24") (pin "1") (pinfunction "1_1") (pintype "passive"))
      (node (ref "C25") (pin "2") (pinfunction "2_2") (pintype "passive"))
      (node (ref "C26") (pin "2") (pinfunction "2_2") (pintype "passive"))
      (node (ref "C27") (pin "2") (pinfunction "2_2") (pintype "passive"))
      (node (ref "C28") (pin "2") (pinfunction "2_2") (pintype "passive"))
      (node (ref "C29") (pin "1") (pinfunction "1_1") (pintype "passive"))
      (node (ref "C30") (pin "1") (pinfunction "1_1") (pintype "passive"))
      (node (ref "C31") (pin "1") (pinfunction "1_1") (pintype "passive"))
      (node (ref "C32") (pin "1") (pinfunction "1_1") (pintype "passive"))
      (node (ref "C33") (pin "1") (pinfunction "1_1") (pintype "passive"))
      (node (ref "C34") (pin "2") (pinfunction "2_2") (pintype "passive"))
      (node (ref "C35") (pin "2") (pinfunction "2_2") (pintype "passive"))
      (node (ref "C36") (pin "1") (pinfunction "1_1") (pintype "passive"))
      (node (ref "C37") (pin "1") (pinfunction "1_1") (pintype "passive"))
      (node (ref "C38") (pin "1") (pinfunction "1_1") (pintype "passive"))
      (node (ref "C5") (pin "1") (pinfunction "1_1") (pintype "passive"))
      (node (ref "C8") (pin "2") (pinfunction "2_2") (pintype "passive"))
      (node (ref "C9") (pin "2") (pinfunction "2_2") (pintype "passive"))
      (node (ref "P1") (pin "1") (pinfunction "1_1") (pintype "passive"))
      (node (ref "P1") (pin "11") (pinfunction "11_11") (pintype "passive"))
      (node (ref "P1") (pin "16") (pinfunction "16_16") (pintype "passive"))
      (node (ref "P1") (pin "17") (pinfunction "17_17") (pintype "passive"))
      (node (ref "P1") (pin "24") (pinfunction "24_24") (pintype "passive"))
      (node (ref "P2") (pin "0") (pinfunction "SHELL_0") (pintype "power_in"))
      (node (ref "P3") (pin "0") (pinfunction "SHELL_0") (pintype "power_in"))
      (node (ref "P4") (pin "1") (pinfunction "1_1") (pintype "passive"))
      (node (ref "P5") (pin "0") (pinfunction "SHELL_0") (pintype "passive"))
      (node (ref "P5") (pin "A1") (pinfunction "GND_A1") (pintype "power_in"))
      (node (ref "P5") (pin "A12") (pinfunction "GND_A12") (pintype "power_in"))
      (node (ref "P5") (pin "B1") (pinfunction "GND_B1") (pintype "power_in"))
      (node (ref "P5") (pin "B12") (pinfunction "GND_B12") (pintype "power_in"))
      (node (ref "P5") (pin "MID") (pinfunction "MID_MID") (pintype "passive"))
      (node (ref "R11") (pin "1") (pinfunction "1_1") (pintype "passive"))
      (node (ref "SP3") (pin "1") (pinfunction "1_1") (pintype "passive"))
      (node (ref "SW1") (pin "2") (pinfunction "2_2") (pintype "passive"))
      (node (ref "SW1") (pin "3") (pinfunction "3_3") (pintype "passive"))
      (node (ref "SW1") (pin "4") (pinfunction "4_4") (pintype "passive"))
      (node (ref "U1") (pin "7") (pinfunction "GND_7") (pintype "power_in"))
      (node (ref "U10") (pin "2") (pinfunction "GND_2") (pintype "power_in"))
      (node (ref "U11") (pin "2") (pinfunction "GND_2") (pintype "power_in"))
      (node (ref "U12") (pin "2") (pinfunction "GND_2") (pintype "power_in"))
      (node (ref "U13") (pin "2") (pinfunction "GND_2") (pintype "power_in"))
      (node (ref "U14") (pin "2") (pinfunction "GND_2") (pintype "power_in"))
      (node (ref "U2") (pin "7") (pinfunction "GND_7") (pintype "power_in"))
      (node (ref "U3") (pin "7") (pinfunction "GND_7") (pintype "power_in"))
      (node (ref "U5") (pin "4") (pinfunction "VSS_4") (pintype "power_in"))
      (node (ref "U6") (pin "7") (pinfunction "GND_7") (pintype "power_in"))
      (node (ref "U7") (pin "Paddle") (pinfunction "GND_Paddle") (pintype "power_in"))
      (node (ref "U8") (pin "12") (pinfunction "DGND_12") (pintype "power_in"))
      (node (ref "U8") (pin "3") (pinfunction "AGND_3") (pintype "power_in"))
      (node (ref "U9") (pin "12") (pinfunction "DGND_12") (pintype "power_in"))
      (node (ref "U9") (pin "3") (pinfunction "AGND_3") (pintype "power_in"))
    )
    (net (code "54") (name "Net-(D1-K)") (class "Default")
      (node (ref "D1") (pin "2") (pinfunction "K_2") (pintype "passive"))
      (node (ref "U7") (pin "41") (pinfunction "RGB2_41") (pintype "open_collector"))
    )
    (net (code "55") (name "Net-(D2-K)") (class "Default")
      (node (ref "D2") (pin "2") (pinfunction "K_2") (pintype "passive"))
      (node (ref "U7") (pin "40") (pinfunction "RGB1_40") (pintype "open_collector"))
    )
    (net (code "56") (name "Net-(D3-K)") (class "Default")
      (node (ref "D3") (pin "2") (pinfunction "K_2") (pintype "passive"))
      (node (ref "U7") (pin "39") (pinfunction "RGB0_39") (pintype "open_collector"))
    )
    (net (code "57") (name "Net-(P5-CC1)") (class "Default")
      (node (ref "P5") (pin "A5") (pinfunction "CC1_A5") (pintype "bidirectional"))
      (node (ref "R11") (pin "2") (pinfunction "2_2") (pintype "passive"))
    )
    (net (code "58") (name "Net-(U4-R)") (class "Default")
      (node (ref "R2") (pin "2") (pinfunction "2_2") (pintype "passive"))
      (node (ref "U4") (pin "2") (pinfunction "R_2") (pintype "passive"))
    )
    (net (code "59") (name "P1.2V") (class "Default")
      (node (ref "C11") (pin "1") (pinfunction "1_1") (pintype "passive"))
      (node (ref "C12") (pin "1") (pinfunction "1_1") (pintype "passive"))
      (node (ref "C13") (pin "1") (pinfunction "1_1") (pintype "passive"))
      (node (ref "C30") (pin "2") (pinfunction "2_2") (pintype "passive"))
      (node (ref "R7") (pin "1") (pinfunction "1_1") (pintype "passive"))
      (node (ref "U10") (pin "5") (pinfunction "OUT_5") (pintype "power_in"))
      (node (ref "U7") (pin "30") (pinfunction "VCC_30") (pintype "power_in"))
      (node (ref "U7") (pin "5") (pinfunction "VCC_5") (pintype "power_in"))
    )
    (net (code "60") (name "P2.5V") (class "Default")
      (node (ref "C21") (pin "1") (pinfunction "1_1") (pintype "passive"))
      (node (ref "C37") (pin "2") (pinfunction "2_2") (pintype "passive"))
      (node (ref "U14") (pin "5") (pinfunction "OUT_5") (pintype "power_in"))
      (node (ref "U7") (pin "24") (pinfunction "VPP_2V5_24") (pintype "power_in"))
    )
    (net (code "61") (name "P3.3V") (class "Default")
      (node (ref "C10") (pin "1") (pinfunction "1_1") (pintype "passive"))
      (node (ref "C14") (pin "1") (pinfunction "1_1") (pintype "passive"))
      (node (ref "C15") (pin "1") (pinfunction "1_1") (pintype "passive"))
      (node (ref "C16") (pin "2") (pinfunction "2_2") (pintype "passive"))
      (node (ref "C19") (pin "1") (pinfunction "1_1") (pintype "passive"))
      (node (ref "C20") (pin "1") (pinfunction "1_1") (pintype "passive"))
      (node (ref "C22") (pin "2") (pinfunction "2_2") (pintype "passive"))
      (node (ref "C23") (pin "1") (pinfunction "1_1") (pintype "passive"))
      (node (ref "C24") (pin "2") (pinfunction "2_2") (pintype "passive"))
      (node (ref "C25") (pin "1") (pinfunction "1_1") (pintype "passive"))
      (node (ref "C26") (pin "1") (pinfunction "1_1") (pintype "passive"))
      (node (ref "C27") (pin "1") (pinfunction "1_1") (pintype "passive"))
      (node (ref "C32") (pin "2") (pinfunction "2_2") (pintype "passive"))
      (node (ref "C34") (pin "1") (pinfunction "1_1") (pintype "passive"))
      (node (ref "C5") (pin "2") (pinfunction "2_2") (pintype "passive"))
      (node (ref "C8") (pin "1") (pinfunction "1_1") (pintype "passive"))
      (node (ref "C9") (pin "1") (pinfunction "1_1") (pintype "passive"))
      (node (ref "P1") (pin "18") (pinfunction "18_18") (pintype "passive"))
      (node (ref "P1") (pin "9") (pinfunction "9_9") (pintype "passive"))
      (node (ref "R10") (pin "1") (pinfunction "1_1") (pintype "passive"))
      (node (ref "R3") (pin "1") (pinfunction "1_1") (pintype "passive"))
      (node (ref "R4") (pin "1") (pinfunction "1_1") (pintype "passive"))
      (node (ref "R5") (pin "1") (pinfunction "1_1") (pintype "passive"))
      (node (ref "R6") (pin "1") (pinfunction "1_1") (pintype "passive"))
      (node (ref "R8") (pin "1") (pinfunction "1_1") (pintype "passive"))
      (node (ref "R9") (pin "1") (pinfunction "1_1") (pintype "passive"))
      (node (ref "U1") (pin "14") (pinfunction "VCC_14") (pintype "power_in"))
      (node (ref "U11") (pin "5") (pinfunction "OUT_5") (pintype "power_in"))
      (node (ref "U12") (pin "3") (pinfunction "EN_3") (pintype "input"))
      (node (ref "U13") (pin "1") (pinfunction "OE_1") (pintype "passive"))
      (node (ref "U13") (pin "4") (pinfunction "Vcc_4") (pintype "power_in"))
      (node (ref "U14") (pin "3") (pinfunction "EN_3") (pintype "input"))
      (node (ref "U2") (pin "14") (pinfunction "VCC_14") (pintype "power_in"))
      (node (ref "U3") (pin "14") (pinfunction "VCC_14") (pintype "power_in"))
      (node (ref "U4") (pin "3") (pinfunction "V+_3") (pintype "power_in"))
      (node (ref "U5") (pin "8") (pinfunction "VCC_8") (pintype "power_in"))
      (node (ref "U6") (pin "14") (pinfunction "VCC_14") (pintype "power_in"))
      (node (ref "U7") (pin "1") (pinfunction "VCCIO_2_1") (pintype "power_in"))
      (node (ref "U7") (pin "22") (pinfunction "SPI_VCCIO1_22") (pintype "power_in"))
      (node (ref "U7") (pin "33") (pinfunction "VCCIO_0_33") (pintype "power_in"))
      (node (ref "U8") (pin "13") (pinfunction "VD_13") (pintype "power_in"))
      (node (ref "U8") (pin "2") (pinfunction "VA_2") (pintype "power_in"))
      (node (ref "U9") (pin "13") (pinfunction "VD_13") (pintype "power_in"))
      (node (ref "U9") (pin "2") (pinfunction "VA_2") (pintype "power_in"))
    )
    (net (code "62") (name "P3.8V") (class "Default")
      (node (ref "C33") (pin "2") (pinfunction "2_2") (pintype "passive"))
      (node (ref "D1") (pin "1") (pinfunction "A_1") (pintype "passive"))
      (node (ref "D2") (pin "1") (pinfunction "A_1") (pintype "passive"))
      (node (ref "D3") (pin "1") (pinfunction "A_1") (pintype "passive"))
      (node (ref "U12") (pin "5") (pinfunction "OUT_5") (pintype "power_in"))
    )
    (net (code "63") (name "VBUS") (class "Default")
      (node (ref "C29") (pin "2") (pinfunction "2_2") (pintype "passive"))
      (node (ref "C31") (pin "2") (pinfunction "2_2") (pintype "passive"))
      (node (ref "C36") (pin "2") (pinfunction "2_2") (pintype "passive"))
      (node (ref "C38") (pin "2") (pinfunction "2_2") (pintype "passive"))
      (node (ref "P1") (pin "12") (pinfunction "12_12") (pintype "passive"))
      (node (ref "P1") (pin "13") (pinfunction "13_13") (pintype "passive"))
      (node (ref "P1") (pin "14") (pinfunction "14_14") (pintype "passive"))
      (node (ref "P5") (pin "A4") (pinfunction "VBUS_A4") (pintype "power_in"))
      (node (ref "P5") (pin "A9") (pinfunction "VBUS_A9") (pintype "power_in"))
      (node (ref "P5") (pin "B4") (pinfunction "VBUS_B4") (pintype "power_in"))
      (node (ref "P5") (pin "B9") (pinfunction "VBUS_B9") (pintype "power_in"))
      (node (ref "SP1") (pin "1") (pinfunction "1_1") (pintype "passive"))
      (node (ref "U10") (pin "1") (pinfunction "IN_1") (pintype "input"))
      (node (ref "U10") (pin "3") (pinfunction "EN_3") (pintype "input"))
      (node (ref "U11") (pin "1") (pinfunction "IN_1") (pintype "input"))
      (node (ref "U11") (pin "3") (pinfunction "EN_3") (pintype "input"))
      (node (ref "U12") (pin "1") (pinfunction "IN_1") (pintype "input"))
      (node (ref "U14") (pin "1") (pinfunction "IN_1") (pintype "input"))
    )
    (net (code "64") (name "unconnected-(P1-Pad2)") (class "Default")
      (node (ref "P1") (pin "2") (pinfunction "2_2") (pintype "passive"))
    )
    (net (code "65") (name "unconnected-(P1-Pad3)") (class "Default")
      (node (ref "P1") (pin "3") (pinfunction "3_3") (pintype "passive"))
    )
    (net (code "66") (name "unconnected-(P1-Pad10)") (class "Default")
      (node (ref "P1") (pin "10") (pinfunction "10_10") (pintype "passive"))
    )
    (net (code "67") (name "unconnected-(P1-Pad15)") (class "Default")
      (node (ref "P1") (pin "15") (pinfunction "15_15") (pintype "passive"))
    )
    (net (code "68") (name "unconnected-(P1-Pad21)") (class "Default")
      (node (ref "P1") (pin "21") (pinfunction "21_21") (pintype "passive"))
    )
    (net (code "69") (name "unconnected-(P1-Pad22)") (class "Default")
      (node (ref "P1") (pin "22") (pinfunction "22_22") (pintype "passive"))
    )
    (net (code "70") (name "unconnected-(P1-Pad23)") (class "Default")
      (node (ref "P1") (pin "23") (pinfunction "23_23") (pintype "passive"))
    )
    (net (code "71") (name "unconnected-(P1-Pad25)") (class "Default")
      (node (ref "P1") (pin "25") (pinfunction "25_25") (pintype "passive"))
    )
    (net (code "72") (name "unconnected-(P1-Pad26)") (class "Default")
      (node (ref "P1") (pin "26") (pinfunction "26_26") (pintype "passive"))
    )
    (net (code "73") (name "unconnected-(P2-SBU1-PadA8)") (class "Default")
      (node (ref "P2") (pin "A8") (pinfunction "SBU1_A8") (pintype "passive+no_connect"))
    )
    (net (code "74") (name "unconnected-(P2-SBU2-PadB8)") (class "Default")
      (node (ref "P2") (pin "B8") (pinfunction "SBU2_B8") (pintype "passive+no_connect"))
    )
    (net (code "75") (name "unconnected-(P2-SSRX1_N-PadB10)") (class "Default")
      (node (ref "P2") (pin "B10") (pinfunction "SSRX1_N_B10") (pintype "bidirectional+no_connect"))
    )
    (net (code "76") (name "unconnected-(P2-SSRX1_P-PadB11)") (class "Default")
      (node (ref "P2") (pin "B11") (pinfunction "SSRX1_P_B11") (pintype "bidirectional+no_connect"))
    )
    (net (code "77") (name "unconnected-(P2-SSRX2_N-PadA10)") (class "Default")
      (node (ref "P2") (pin "A10") (pinfunction "SSRX2_N_A10") (pintype "bidirectional+no_connect"))
    )
    (net (code "78") (name "unconnected-(P2-SSRX2_P-PadA11)") (class "Default")
      (node (ref "P2") (pin "A11") (pinfunction "SSRX2_P_A11") (pintype "bidirectional+no_connect"))
    )
    (net (code "79") (name "unconnected-(P2-SSTX1_N-PadA3)") (class "Default")
      (node (ref "P2") (pin "A3") (pinfunction "SSTX1_N_A3") (pintype "bidirectional+no_connect"))
    )
    (net (code "80") (name "unconnected-(P2-SSTX1_P-PadA2)") (class "Default")
      (node (ref "P2") (pin "A2") (pinfunction "SSTX1_P_A2") (pintype "bidirectional+no_connect"))
    )
    (net (code "81") (name "unconnected-(P2-SSTX2_N-PadB3)") (class "Default")
      (node (ref "P2") (pin "B3") (pinfunction "SSTX2_N_B3") (pintype "power_in+no_connect"))
    )
    (net (code "82") (name "unconnected-(P2-SSTX2_P-PadB2)") (class "Default")
      (node (ref "P2") (pin "B2") (pinfunction "SSTX2_P_B2") (pintype "power_in+no_connect"))
    )
    (net (code "83") (name "unconnected-(P3-CC1-PadA5)") (class "Default")
      (node (ref "P3") (pin "A5") (pinfunction "CC1_A5") (pintype "bidirectional+no_connect"))
    )
    (net (code "84") (name "unconnected-(P3-CC2-PadB5)") (class "Default")
      (node (ref "P3") (pin "B5") (pinfunction "CC2_B5") (pintype "bidirectional+no_connect"))
    )
    (net (code "85") (name "unconnected-(P3-GND-PadA1)") (class "Default")
      (node (ref "P3") (pin "A1") (pinfunction "GND_A1") (pintype "power_in+no_connect"))
    )
    (net (code "86") (name "unconnected-(P3-GND-PadB1)") (class "Default")
      (node (ref "P3") (pin "B1") (pinfunction "GND_B1") (pintype "power_in+no_connect"))
    )
    (net (code "87") (name "unconnected-(P3-GND-PadB12)") (class "Default")
      (node (ref "P3") (pin "B12") (pinfunction "GND_B12") (pintype "power_in+no_connect"))
    )
    (net (code "88") (name "unconnected-(P3-SBU1-PadA8)") (class "Default")
      (node (ref "P3") (pin "A8") (pinfunction "SBU1_A8") (pintype "passive+no_connect"))
    )
    (net (code "89") (name "unconnected-(P3-SBU2-PadB8)") (class "Default")
      (node (ref "P3") (pin "B8") (pinfunction "SBU2_B8") (pintype "passive+no_connect"))
    )
    (net (code "90") (name "unconnected-(P3-SSRX1_N-PadB10)") (class "Default")
      (node (ref "P3") (pin "B10") (pinfunction "SSRX1_N_B10") (pintype "bidirectional+no_connect"))
    )
    (net (code "91") (name "unconnected-(P3-SSRX1_P-PadB11)") (class "Default")
      (node (ref "P3") (pin "B11") (pinfunction "SSRX1_P_B11") (pintype "bidirectional+no_connect"))
    )
    (net (code "92") (name "unconnected-(P3-SSRX2_N-PadA10)") (class "Default")
      (node (ref "P3") (pin "A10") (pinfunction "SSRX2_N_A10") (pintype "bidirectional+no_connect"))
    )
    (net (code "93") (name "unconnected-(P3-SSRX2_P-PadA11)") (class "Default")
      (node (ref "P3") (pin "A11") (pinfunction "SSRX2_P_A11") (pintype "bidirectional+no_connect"))
    )
    (net (code "94") (name "unconnected-(P3-SSTX1_N-PadA3)") (class "Default")
      (node (ref "P3") (pin "A3") (pinfunction "SSTX1_N_A3") (pintype "bidirectional+no_connect"))
    )
    (net (code "95") (name "unconnected-(P3-SSTX1_P-PadA2)") (class "Default")
      (node (ref "P3") (pin "A2") (pinfunction "SSTX1_P_A2") (pintype "bidirectional+no_connect"))
    )
    (net (code "96") (name "unconnected-(P3-SSTX2_N-PadB3)") (class "Default")
      (node (ref "P3") (pin "B3") (pinfunction "SSTX2_N_B3") (pintype "power_in+no_connect"))
    )
    (net (code "97") (name "unconnected-(P3-SSTX2_P-PadB2)") (class "Default")
      (node (ref "P3") (pin "B2") (pinfunction "SSTX2_P_B2") (pintype "power_in+no_connect"))
    )
    (net (code "98") (name "unconnected-(P3-VBUS-PadA4)") (class "Default")
      (node (ref "P3") (pin "A4") (pinfunction "VBUS_A4") (pintype "power_in+no_connect"))
    )
    (net (code "99") (name "unconnected-(P3-VBUS-PadB4)") (class "Default")
      (node (ref "P3") (pin "B4") (pinfunction "VBUS_B4") (pintype "power_in+no_connect"))
    )
    (net (code "100") (name "unconnected-(P3-VBUS-PadB9)") (class "Default")
      (node (ref "P3") (pin "B9") (pinfunction "VBUS_B9") (pintype "power_in+no_connect"))
    )
    (net (code "101") (name "unconnected-(P5-CC2-PadB5)") (class "Default")
      (node (ref "P5") (pin "B5") (pinfunction "CC2_B5") (pintype "bidirectional+no_connect"))
    )
    (net (code "102") (name "unconnected-(P5-D1_N-PadA7)") (class "Default")
      (node (ref "P5") (pin "A7") (pinfunction "D1_N_A7") (pintype "bidirectional+no_connect"))
    )
    (net (code "103") (name "unconnected-(P5-D1_P-PadA6)") (class "Default")
      (node (ref "P5") (pin "A6") (pinfunction "D1_P_A6") (pintype "bidirectional+no_connect"))
    )
    (net (code "104") (name "unconnected-(P5-D2_N-PadB7)") (class "Default")
      (node (ref "P5") (pin "B7") (pinfunction "D2_N_B7") (pintype "bidirectional+no_connect"))
    )
    (net (code "105") (name "unconnected-(P5-D2_P-PadB6)") (class "Default")
      (node (ref "P5") (pin "B6") (pinfunction "D2_P_B6") (pintype "bidirectional+no_connect"))
    )
    (net (code "106") (name "unconnected-(P5-SBU1-PadA8)") (class "Default")
      (node (ref "P5") (pin "A8") (pinfunction "SBU1_A8") (pintype "passive+no_connect"))
    )
    (net (code "107") (name "unconnected-(P5-SBU2-PadB8)") (class "Default")
      (node (ref "P5") (pin "B8") (pinfunction "SBU2_B8") (pintype "passive+no_connect"))
    )
    (net (code "108") (name "unconnected-(P5-SSRX1_N-PadB10)") (class "Default")
      (node (ref "P5") (pin "B10") (pinfunction "SSRX1_N_B10") (pintype "bidirectional+no_connect"))
    )
    (net (code "109") (name "unconnected-(P5-SSRX1_P-PadB11)") (class "Default")
      (node (ref "P5") (pin "B11") (pinfunction "SSRX1_P_B11") (pintype "bidirectional+no_connect"))
    )
    (net (code "110") (name "unconnected-(P5-SSRX2_N-PadA10)") (class "Default")
      (node (ref "P5") (pin "A10") (pinfunction "SSRX2_N_A10") (pintype "bidirectional+no_connect"))
    )
    (net (code "111") (name "unconnected-(P5-SSRX2_P-PadA11)") (class "Default")
      (node (ref "P5") (pin "A11") (pinfunction "SSRX2_P_A11") (pintype "bidirectional+no_connect"))
    )
    (net (code "112") (name "unconnected-(P5-SSTX1_N-PadA3)") (class "Default")
      (node (ref "P5") (pin "A3") (pinfunction "SSTX1_N_A3") (pintype "bidirectional+no_connect"))
    )
    (net (code "113") (name "unconnected-(P5-SSTX1_P-PadA2)") (class "Default")
      (node (ref "P5") (pin "A2") (pinfunction "SSTX1_P_A2") (pintype "bidirectional+no_connect"))
    )
    (net (code "114") (name "unconnected-(P5-SSTX2_N-PadB3)") (class "Default")
      (node (ref "P5") (pin "B3") (pinfunction "SSTX2_N_B3") (pintype "power_in+no_connect"))
    )
    (net (code "115") (name "unconnected-(P5-SSTX2_P-PadB2)") (class "Default")
      (node (ref "P5") (pin "B2") (pinfunction "SSTX2_P_B2") (pintype "power_in+no_connect"))
    )
    (net (code "116") (name "unconnected-(SW1-Pad1)") (class "Default")
      (node (ref "SW1") (pin "1") (pinfunction "1_1") (pintype "passive"))
    )
    (net (code "117") (name "unconnected-(U7-IOB_23B-Pad21)") (class "Default")
      (node (ref "U7") (pin "21") (pinfunction "IOB_23B_21") (pintype "bidirectional"))
    )
    (net (code "118") (name "unconnected-(U7-IOT_36B-Pad25)") (class "Default")
      (node (ref "U7") (pin "25") (pinfunction "IOT_36B_25") (pintype "bidirectional"))
    )
    (net (code "119") (name "unconnected-(U7-IOT_37A-Pad23)") (class "Default")
      (node (ref "U7") (pin "23") (pinfunction "IOT_37A_23") (pintype "bidirectional"))
    )
    (net (code "120") (name "unconnected-(U7-IOT_39A-Pad26)") (class "Default")
      (node (ref "U7") (pin "26") (pinfunction "IOT_39A_26") (pintype "bidirectional"))
    )
  )
)
